# front.net
KiCad netlist of a schematic drawn in EAGLE
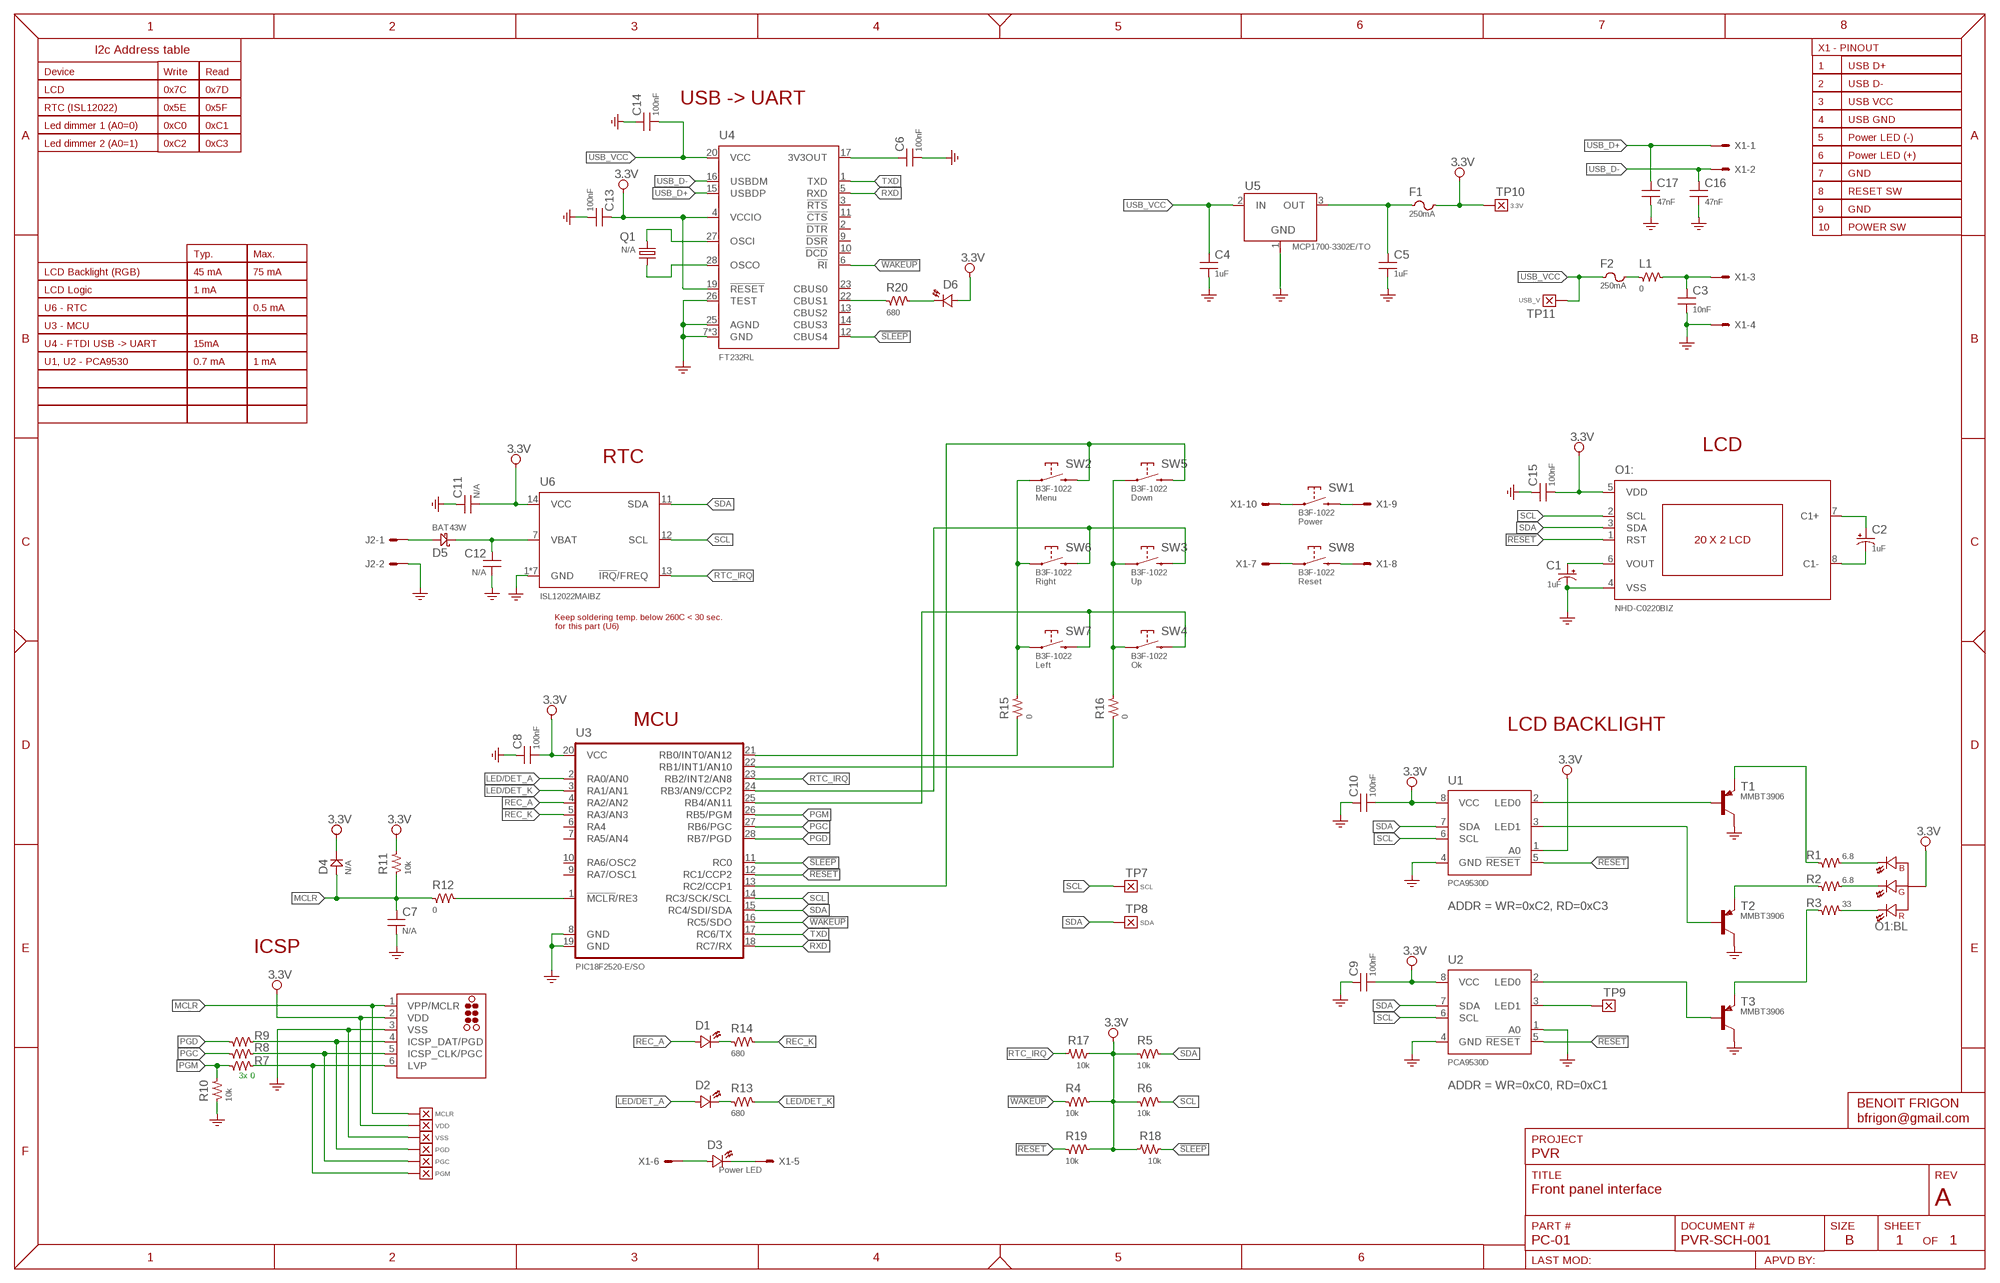
[diagram p0: schematic, sheet 1]

(export (version "E")
  (design (tool "Eeschema 10.0.6"))
  (components
    (comp (ref "C1")
      (value "1uF")
      (footprint "eagle-import:CAP_S0805")
      (libsource (lib "eagle-import") (part "CAP-E-S0805"))
    )
    (comp (ref "C2")
      (value "1uF")
      (footprint "eagle-import:CAP_S0805")
      (libsource (lib "eagle-import") (part "CAP-E-S0805"))
    )
    (comp (ref "C3")
      (value "10nF")
      (footprint "eagle-import:SMD_0805")
      (libsource (lib "eagle-import") (part "CAP-0805"))
    )
    (comp (ref "C4")
      (value "1uF")
      (footprint "eagle-import:SMD_0805")
      (libsource (lib "eagle-import") (part "CAP-0805"))
    )
    (comp (ref "C5")
      (value "1uF")
      (footprint "eagle-import:SMD_0805")
      (libsource (lib "eagle-import") (part "CAP-0805"))
    )
    (comp (ref "C6")
      (value "100nF")
      (footprint "eagle-import:SMD_0603")
      (libsource (lib "eagle-import") (part "CAP-0603"))
    )
    (comp (ref "C7")
      (value "N/A")
      (footprint "eagle-import:SMD_0603")
      (libsource (lib "eagle-import") (part "CAP-0603"))
    )
    (comp (ref "C8")
      (value "100nF")
      (footprint "eagle-import:SMD_0603")
      (libsource (lib "eagle-import") (part "CAP-0603"))
    )
    (comp (ref "C9")
      (value "100nF")
      (footprint "eagle-import:SMD_0603")
      (libsource (lib "eagle-import") (part "CAP-0603"))
    )
    (comp (ref "C10")
      (value "100nF")
      (footprint "eagle-import:SMD_0603")
      (libsource (lib "eagle-import") (part "CAP-0603"))
    )
    (comp (ref "C11")
      (value "N/A")
      (footprint "eagle-import:SMD_0603")
      (libsource (lib "eagle-import") (part "CAP-0603"))
    )
    (comp (ref "C12")
      (value "N/A")
      (footprint "eagle-import:SMD_0805")
      (libsource (lib "eagle-import") (part "CAP-0805"))
    )
    (comp (ref "C13")
      (value "100nF")
      (footprint "eagle-import:SMD_0603")
      (libsource (lib "eagle-import") (part "CAP-0603"))
    )
    (comp (ref "C14")
      (value "100nF")
      (footprint "eagle-import:SMD_0603")
      (description "{DESCRIPTION} - SMT 0603 - {value}")
      (fields (field (name "PACKAGE") "SMT 0603"))
      (libsource (lib "eagle-import") (part "CAP-0603"))
    )
    (comp (ref "C15")
      (value "100nF")
      (footprint "eagle-import:SMD_0603")
      (libsource (lib "eagle-import") (part "CAP-0603"))
    )
    (comp (ref "C16")
      (value "47nF")
      (footprint "eagle-import:SMD_0603")
      (libsource (lib "eagle-import") (part "CAP-0603"))
    )
    (comp (ref "C17")
      (value "47nF")
      (footprint "eagle-import:SMD_0603")
      (libsource (lib "eagle-import") (part "CAP-0603"))
    )
    (comp (ref "D1")
      (value "{ATTR:COLOR}")
      (footprint "eagle-import:LED_2X5")
      (fields (field (name "COLOR") "Red"))
      (libsource (lib "eagle-import") (part "LED-2X5"))
    )
    (comp (ref "D2")
      (value "{ATTR:COLOR}")
      (footprint "eagle-import:LED_2X5")
      (libsource (lib "eagle-import") (part "LED-2X5"))
    )
    (comp (ref "D3")
      (value "{ATTR:COLOR}")
      (footprint "eagle-import:LED_2X5")
      (fields (field (name "ID") "Power LED"))
      (libsource (lib "eagle-import") (part "LED-2X5"))
    )
    (comp (ref "D4")
      (value "N/A")
      (footprint "eagle-import:DIODE_0603")
      (libsource (lib "eagle-import") (part "DIODE-0603"))
    )
    (comp (ref "D5")
      (value "BAT43W")
      (footprint "eagle-import:SOD-323")
      (libsource (lib "eagle-import") (part "DIODE_SCHOTTKY-SOD323"))
    )
    (comp (ref "D6")
      (value "LED-0805")
      (footprint "eagle-import:CHIPLED_0805")
      (libsource (lib "eagle-import") (part "LED-0805"))
    )
    (comp (ref "F1")
      (value "250mA")
      (footprint "eagle-import:SMD_1206")
      (libsource (lib "eagle-import") (part "FUSE1206"))
    )
    (comp (ref "F2")
      (value "250mA")
      (footprint "eagle-import:SMD_1206")
      (libsource (lib "eagle-import") (part "FUSE1206"))
    )
    (comp (ref "J1")
      (value "TC2030-MCP")
      (footprint "eagle-import:TC2030-MCP")
      (fields (field (name "MFG") "Tag-Connect"))
      (libsource (lib "eagle-import") (part "TC2030-MCP"))
    )
    (comp (ref "J2")
      (value "SNG-2MM-HEADER-02-V")
      (footprint "eagle-import:DF3X-2P-2DSA")
      (fields (field (name "MFG") "Hirose Electronic") (field (name "NO_BOM") "1"))
      (libsource (lib "eagle-import") (part "SNG-2MM-HEADER-02-V"))
    )
    (comp (ref "L1")
      (value "0")
      (footprint "eagle-import:SMD_0805")
      (libsource (lib "eagle-import") (part "RES-0805"))
    )
    (comp (ref "O1")
      (value "NHD-C0220BIZ")
      (footprint "eagle-import:NHD-CO220BIZ")
      (fields (field (name "MFG") "Newheaven Display"))
      (libsource (lib "eagle-import") (part "NHD-C0220BIZ"))
    )
    (comp (ref "Q1")
      (value "N/A")
      (footprint "eagle-import:MM20SS")
      (libsource (lib "eagle-import") (part "XTALMM20SS"))
    )
    (comp (ref "R1")
      (value "6.8")
      (footprint "eagle-import:SMD_1206")
      (description "{DESCRIPTION} - SMT 1206 - {VALUE}")
      (fields (field (name "PACKAGE") "SMT 1206"))
      (libsource (lib "eagle-import") (part "RES-1206"))
    )
    (comp (ref "R2")
      (value "6.8")
      (footprint "eagle-import:SMD_1206")
      (description "{DESCRIPTION} - SMT 1206 - {VALUE}")
      (fields (field (name "PACKAGE") "SMT 1206"))
      (libsource (lib "eagle-import") (part "RES-1206"))
    )
    (comp (ref "R3")
      (value "33")
      (footprint "eagle-import:SMD_1206")
      (description "{DESCRIPTION} - SMT 1206 - {VALUE}")
      (fields (field (name "PACKAGE") "SMT 1206"))
      (libsource (lib "eagle-import") (part "RES-1206"))
    )
    (comp (ref "R4")
      (value "10k")
      (footprint "eagle-import:SMD_0805")
      (libsource (lib "eagle-import") (part "RES-0805"))
    )
    (comp (ref "R5")
      (value "10k")
      (footprint "eagle-import:SMD_0805")
      (libsource (lib "eagle-import") (part "RES-0805"))
    )
    (comp (ref "R6")
      (value "10k")
      (footprint "eagle-import:SMD_0805")
      (libsource (lib "eagle-import") (part "RES-0805"))
    )
    (comp (ref "R7")
      (value "0")
      (footprint "eagle-import:SMD_0603")
      (description "{DESCRIPTION} - SMT 0603 - {VALUE}")
      (fields (field (name "PACKAGE") "SMT 0603"))
      (libsource (lib "eagle-import") (part "RES-0603"))
    )
    (comp (ref "R8")
      (value "0")
      (footprint "eagle-import:SMD_0603")
      (description "{DESCRIPTION} - SMT 0603 - {VALUE}")
      (fields (field (name "PACKAGE") "SMT 0603"))
      (libsource (lib "eagle-import") (part "RES-0603"))
    )
    (comp (ref "R9")
      (value "0")
      (footprint "eagle-import:SMD_0603")
      (description "{DESCRIPTION} - SMT 0603 - {VALUE}")
      (fields (field (name "PACKAGE") "SMT 0603"))
      (libsource (lib "eagle-import") (part "RES-0603"))
    )
    (comp (ref "R10")
      (value "10k")
      (footprint "eagle-import:SMD_0603")
      (description "{DESCRIPTION} - SMT 0603 - {VALUE}")
      (fields (field (name "PACKAGE") "SMT 0603"))
      (libsource (lib "eagle-import") (part "RES-0603"))
    )
    (comp (ref "R11")
      (value "10k")
      (footprint "eagle-import:SMD_0603")
      (libsource (lib "eagle-import") (part "RES-0603"))
    )
    (comp (ref "R12")
      (value "0")
      (footprint "eagle-import:SMD_0603")
      (libsource (lib "eagle-import") (part "RES-0603"))
    )
    (comp (ref "R13")
      (value "680")
      (footprint "eagle-import:SMD_0805")
      (libsource (lib "eagle-import") (part "RES-0805"))
    )
    (comp (ref "R14")
      (value "680")
      (footprint "eagle-import:SMD_0805")
      (description "{DESCRIPTION} - SMT 0805 - {VALUE}")
      (fields (field (name "PACKAGE") "SMT 0805"))
      (libsource (lib "eagle-import") (part "RES-0805"))
    )
    (comp (ref "R15")
      (value "0")
      (footprint "eagle-import:SMD_0805")
      (libsource (lib "eagle-import") (part "RES-0805"))
    )
    (comp (ref "R16")
      (value "0")
      (footprint "eagle-import:SMD_0805")
      (libsource (lib "eagle-import") (part "RES-0805"))
    )
    (comp (ref "R17")
      (value "10k")
      (footprint "eagle-import:SMD_0603")
      (description "{DESCRIPTION} - SMT 0603 - {VALUE}")
      (fields (field (name "PACKAGE") "SMT 0603"))
      (libsource (lib "eagle-import") (part "RES-0603"))
    )
    (comp (ref "R18")
      (value "10k")
      (footprint "eagle-import:SMD_0805")
      (description "{DESCRIPTION} - SMT 0805 - {VALUE}")
      (fields (field (name "PACKAGE") "SMT 0805"))
      (libsource (lib "eagle-import") (part "RES-0805"))
    )
    (comp (ref "R19")
      (value "10k")
      (footprint "eagle-import:SMD_0805")
      (description "{DESCRIPTION} - SMT 0805 - {VALUE}")
      (fields (field (name "PACKAGE") "SMT 0805"))
      (libsource (lib "eagle-import") (part "RES-0805"))
    )
    (comp (ref "R20")
      (value "680")
      (footprint "eagle-import:SMD_0805")
      (libsource (lib "eagle-import") (part "RES-0805"))
    )
    (comp (ref "SW1")
      (value "B3F-1022")
      (footprint "eagle-import:B3F-10XX")
      (fields (field (name "MFG") "Omron Electronics") (field (name "KEY") "Power"))
      (libsource (lib "eagle-import") (part "B3F-?1022"))
    )
    (comp (ref "SW2")
      (value "B3F-1022")
      (footprint "eagle-import:B3F-10XX")
      (fields (field (name "MFG") "Omron Electronics") (field (name "KEY") "Menu"))
      (libsource (lib "eagle-import") (part "B3F-?1022"))
    )
    (comp (ref "SW3")
      (value "B3F-1022")
      (footprint "eagle-import:B3F-10XX")
      (fields (field (name "MFG") "Omron Electronics") (field (name "KEY") "Up"))
      (libsource (lib "eagle-import") (part "B3F-?1022"))
    )
    (comp (ref "SW4")
      (value "B3F-1022")
      (footprint "eagle-import:B3F-10XX")
      (fields (field (name "MFG") "Omron Electronics") (field (name "KEY") "Ok"))
      (libsource (lib "eagle-import") (part "B3F-?1022"))
    )
    (comp (ref "SW5")
      (value "B3F-1022")
      (footprint "eagle-import:B3F-10XX")
      (fields (field (name "MFG") "Omron Electronics") (field (name "KEY") "Down"))
      (libsource (lib "eagle-import") (part "B3F-?1022"))
    )
    (comp (ref "SW6")
      (value "B3F-1022")
      (footprint "eagle-import:B3F-10XX")
      (fields (field (name "MFG") "Omron Electronics") (field (name "KEY") "Right"))
      (libsource (lib "eagle-import") (part "B3F-?1022"))
    )
    (comp (ref "SW7")
      (value "B3F-1022")
      (footprint "eagle-import:B3F-10XX")
      (fields (field (name "MFG") "Omron Electronics") (field (name "KEY") "Left"))
      (libsource (lib "eagle-import") (part "B3F-?1022"))
    )
    (comp (ref "SW8")
      (value "B3F-1022")
      (footprint "eagle-import:B3F-10XX")
      (fields (field (name "MFG") "Omron Electronics") (field (name "KEY") "Reset"))
      (libsource (lib "eagle-import") (part "B3F-?1022"))
    )
    (comp (ref "T1")
      (value "MMBT3906")
      (footprint "eagle-import:SOT23-BEC")
      (libsource (lib "eagle-import") (part "-PNP-SOT23-BEC"))
    )
    (comp (ref "T2")
      (value "MMBT3906")
      (footprint "eagle-import:SOT23-BEC")
      (fields (field (name "SKU") "{VALUE}"))
      (libsource (lib "eagle-import") (part "-PNP-SOT23-BEC"))
    )
    (comp (ref "T3")
      (value "MMBT3906")
      (footprint "eagle-import:SOT23-BEC")
      (fields (field (name "SKU") "{VALUE}"))
      (libsource (lib "eagle-import") (part "-PNP-SOT23-BEC"))
    )
    (comp (ref "TP1")
      (value "MCLR")
      (footprint "eagle-import:TP_050")
      (libsource (lib "eagle-import") (part "TEST_POINT-050"))
    )
    (comp (ref "TP2")
      (value "VDD")
      (footprint "eagle-import:TP_050")
      (libsource (lib "eagle-import") (part "TEST_POINT-050"))
    )
    (comp (ref "TP3")
      (value "VSS")
      (footprint "eagle-import:TP_050")
      (libsource (lib "eagle-import") (part "TEST_POINT-050"))
    )
    (comp (ref "TP4")
      (value "PGD")
      (footprint "eagle-import:TP_050")
      (libsource (lib "eagle-import") (part "TEST_POINT-050"))
    )
    (comp (ref "TP5")
      (value "PGC")
      (footprint "eagle-import:TP_050")
      (libsource (lib "eagle-import") (part "TEST_POINT-050"))
    )
    (comp (ref "TP6")
      (value "PGM")
      (footprint "eagle-import:TP_050")
      (libsource (lib "eagle-import") (part "TEST_POINT-050"))
    )
    (comp (ref "TP7")
      (value "SCL")
      (footprint "eagle-import:TP_050")
      (libsource (lib "eagle-import") (part "TEST_POINT-050"))
    )
    (comp (ref "TP8")
      (value "SDA")
      (footprint "eagle-import:TP_050")
      (libsource (lib "eagle-import") (part "TEST_POINT-050"))
    )
    (comp (ref "TP9")
      (value "TEST_POINT-050")
      (footprint "eagle-import:TP_050")
      (libsource (lib "eagle-import") (part "TEST_POINT-050"))
    )
    (comp (ref "TP10")
      (value "3.3V")
      (footprint "eagle-import:TP_050")
      (libsource (lib "eagle-import") (part "TEST_POINT-050"))
    )
    (comp (ref "TP11")
      (value "USB_V")
      (footprint "eagle-import:TP_050")
      (libsource (lib "eagle-import") (part "TEST_POINT-050"))
    )
    (comp (ref "U1")
      (value "PCA9530D")
      (footprint "eagle-import:SOIC8")
      (fields (field (name "MFG") "NXP Semiconductors") (field (name "ADDR") "WR=0xC2, RD=0xC3"))
      (libsource (lib "eagle-import") (part "PCA9530D"))
    )
    (comp (ref "U2")
      (value "PCA9530D")
      (footprint "eagle-import:SOIC8")
      (fields (field (name "MFG") "NXP Semiconductors") (field (name "ADDR") "WR=0xC0, RD=0xC1"))
      (libsource (lib "eagle-import") (part "PCA9530D"))
    )
    (comp (ref "U3")
      (value "PIC18F2520-E/SO")
      (footprint "eagle-import:SOIC28")
      (libsource (lib "eagle-import") (part "PIC18F520-?E/SO2"))
    )
    (comp (ref "U4")
      (value "FT232RL")
      (footprint "eagle-import:SSOP28")
      (libsource (lib "eagle-import") (part "FT232RL"))
    )
    (comp (ref "U5")
      (value "MCP1700-3302E/TO")
      (footprint "eagle-import:TO92")
      (fields (field (name "MFG") "Microchip"))
      (libsource (lib "eagle-import") (part "MCP1700-?TO3302E/"))
    )
    (comp (ref "U6")
      (value "ISL12022MAIBZ")
      (footprint "eagle-import:SOIC20W")
      (libsource (lib "eagle-import") (part "ISL12022MAIBZ"))
    )
    (comp (ref "X1")
      (value "DL-100-HEADER-10-V")
      (footprint "eagle-import:534206-5")
      (fields
        (field (name "MFG") "Tyco Electronics")
        (field (name "MFG_1") "Sullins Connector Solutions")
        (field (name "SKU") "SIP110-PPPC-D05-ST-BK")
      )
      (libsource (lib "eagle-import") (part "DL-100-HEADER-10-V"))
    )
  )
  (nets
    (net (code "1") (name "/~{RESET}") (class "Default")
      (node (ref "O1") (pin "1") (pinfunction "RST_1") (pintype "bidirectional"))
      (node (ref "R19") (pin "1") (pinfunction "1_1") (pintype "passive"))
      (node (ref "U1") (pin "5") (pinfunction "~{RESET}_5") (pintype "input"))
      (node (ref "U2") (pin "5") (pinfunction "~{RESET}_5") (pintype "input"))
      (node (ref "U3") (pin "12") (pinfunction "RC1/CCP2_12") (pintype "bidirectional"))
    )
    (net (code "2") (name "/~{SLEEP}") (class "Default")
      (node (ref "R18") (pin "1") (pinfunction "1_1") (pintype "passive"))
      (node (ref "U3") (pin "11") (pinfunction "RC0_11") (pintype "bidirectional"))
      (node (ref "U4") (pin "12") (pinfunction "CBUS4_12") (pintype "bidirectional"))
    )
    (net (code "3") (name "/~{WAKEUP}") (class "Default")
      (node (ref "R4") (pin "1") (pinfunction "1_1") (pintype "passive"))
      (node (ref "U3") (pin "16") (pinfunction "RC5/SDO_16") (pintype "bidirectional"))
      (node (ref "U4") (pin "6") (pinfunction "~{RI}_6") (pintype "bidirectional"))
    )
    (net (code "4") (name "3.3V") (class "Default")
      (node (ref "C10") (pin "2") (pinfunction "2_2") (pintype "passive"))
      (node (ref "C11") (pin "2") (pinfunction "2_2") (pintype "passive"))
      (node (ref "C13") (pin "1") (pinfunction "1_1") (pintype "passive"))
      (node (ref "C15") (pin "2") (pinfunction "2_2") (pintype "passive"))
      (node (ref "C8") (pin "2") (pinfunction "2_2") (pintype "passive"))
      (node (ref "C9") (pin "2") (pinfunction "2_2") (pintype "passive"))
      (node (ref "D4") (pin "K") (pinfunction "K_K") (pintype "passive"))
      (node (ref "D6") (pin "A") (pinfunction "A_A") (pintype "passive"))
      (node (ref "F1") (pin "2") (pinfunction "2_2") (pintype "passive"))
      (node (ref "J1") (pin "2") (pinfunction "VDD_2") (pintype "power_in"))
      (node (ref "O1") (pin "5") (pinfunction "VDD_5") (pintype "bidirectional"))
      (node (ref "O1") (pin "A") (pinfunction "A_A") (pintype "passive"))
      (node (ref "R11") (pin "2") (pinfunction "2_2") (pintype "passive"))
      (node (ref "R17") (pin "1") (pinfunction "1_1") (pintype "passive"))
      (node (ref "R18") (pin "2") (pinfunction "2_2") (pintype "passive"))
      (node (ref "R19") (pin "2") (pinfunction "2_2") (pintype "passive"))
      (node (ref "R4") (pin "2") (pinfunction "2_2") (pintype "passive"))
      (node (ref "R5") (pin "1") (pinfunction "1_1") (pintype "passive"))
      (node (ref "R6") (pin "1") (pinfunction "1_1") (pintype "passive"))
      (node (ref "TP10") (pin "1") (pinfunction "P$1_1") (pintype "bidirectional"))
      (node (ref "TP2") (pin "1") (pinfunction "P$1_1") (pintype "bidirectional"))
      (node (ref "U1") (pin "1") (pinfunction "A0_1") (pintype "bidirectional"))
      (node (ref "U1") (pin "8") (pinfunction "VCC_8") (pintype "power_in"))
      (node (ref "U2") (pin "8") (pinfunction "VCC_8") (pintype "power_in"))
      (node (ref "U3") (pin "20") (pinfunction "VCC_20") (pintype "power_in"))
      (node (ref "U4") (pin "19") (pinfunction "~{RESET}_19") (pintype "bidirectional"))
      (node (ref "U4") (pin "4") (pinfunction "VCCIO_4") (pintype "bidirectional"))
      (node (ref "U6") (pin "14") (pinfunction "VCC_14") (pintype "bidirectional"))
    )
    (net (code "5") (name "GND") (class "Default")
      (node (ref "C1") (pin "-") (pinfunction "-_-") (pintype "passive"))
      (node (ref "C10") (pin "1") (pinfunction "1_1") (pintype "passive"))
      (node (ref "C11") (pin "1") (pinfunction "1_1") (pintype "passive"))
      (node (ref "C12") (pin "2") (pinfunction "2_2") (pintype "passive"))
      (node (ref "C13") (pin "2") (pinfunction "2_2") (pintype "passive"))
      (node (ref "C14") (pin "1") (pinfunction "1_1") (pintype "passive"))
      (node (ref "C15") (pin "1") (pinfunction "1_1") (pintype "passive"))
      (node (ref "C16") (pin "2") (pinfunction "2_2") (pintype "passive"))
      (node (ref "C17") (pin "2") (pinfunction "2_2") (pintype "passive"))
      (node (ref "C3") (pin "2") (pinfunction "2_2") (pintype "passive"))
      (node (ref "C4") (pin "2") (pinfunction "2_2") (pintype "passive"))
      (node (ref "C5") (pin "2") (pinfunction "2_2") (pintype "passive"))
      (node (ref "C6") (pin "2") (pinfunction "2_2") (pintype "passive"))
      (node (ref "C7") (pin "2") (pinfunction "2_2") (pintype "passive"))
      (node (ref "C8") (pin "1") (pinfunction "1_1") (pintype "passive"))
      (node (ref "C9") (pin "1") (pinfunction "1_1") (pintype "passive"))
      (node (ref "J1") (pin "3") (pinfunction "VSS_3") (pintype "power_in"))
      (node (ref "J2") (pin "2") (pinfunction "S_2") (pintype "bidirectional"))
      (node (ref "O1") (pin "4") (pinfunction "VSS_4") (pintype "bidirectional"))
      (node (ref "R10") (pin "1") (pinfunction "1_1") (pintype "passive"))
      (node (ref "T1") (pin "C") (pinfunction "C_C") (pintype "passive"))
      (node (ref "T2") (pin "C") (pinfunction "C_C") (pintype "passive"))
      (node (ref "T3") (pin "C") (pinfunction "C_C") (pintype "passive"))
      (node (ref "TP3") (pin "1") (pinfunction "P$1_1") (pintype "bidirectional"))
      (node (ref "U1") (pin "4") (pinfunction "GND_4") (pintype "power_in"))
      (node (ref "U2") (pin "1") (pinfunction "A0_1") (pintype "bidirectional"))
      (node (ref "U2") (pin "4") (pinfunction "GND_4") (pintype "power_in"))
      (node (ref "U3") (pin "19") (pinfunction "GND_19") (pintype "power_in"))
      (node (ref "U3") (pin "8") (pinfunction "GND_8") (pintype "power_in"))
      (node (ref "U4") (pin "18") (pinfunction "GND_18") (pintype "bidirectional"))
      (node (ref "U4") (pin "21") (pinfunction "GND_21") (pintype "bidirectional"))
      (node (ref "U4") (pin "25") (pinfunction "AGND_25") (pintype "bidirectional"))
      (node (ref "U4") (pin "26") (pinfunction "TEST_26") (pintype "bidirectional"))
      (node (ref "U4") (pin "7") (pinfunction "GND_7") (pintype "bidirectional"))
      (node (ref "U5") (pin "1") (pinfunction "GND_1") (pintype "power_in"))
      (node (ref "U6") (pin "1") (pinfunction "GND_1") (pintype "bidirectional"))
      (node (ref "U6") (pin "18") (pinfunction "GND_18") (pintype "bidirectional"))
      (node (ref "U6") (pin "19") (pinfunction "GND_19") (pintype "bidirectional"))
      (node (ref "U6") (pin "2") (pinfunction "GND_2") (pintype "bidirectional"))
      (node (ref "U6") (pin "20") (pinfunction "GND_20") (pintype "bidirectional"))
      (node (ref "U6") (pin "3") (pinfunction "GND_3") (pintype "bidirectional"))
      (node (ref "U6") (pin "8") (pinfunction "GND_8") (pintype "bidirectional"))
      (node (ref "X1") (pin "4") (pinfunction "S_4") (pintype "bidirectional"))
    )
    (net (code "6") (name "LED{slash}DET_A") (class "Default")
      (node (ref "D2") (pin "A") (pinfunction "A_A") (pintype "passive"))
      (node (ref "U3") (pin "2") (pinfunction "RA0/AN0_2") (pintype "bidirectional"))
    )
    (net (code "7") (name "LED{slash}DET_K") (class "Default")
      (node (ref "R13") (pin "2") (pinfunction "2_2") (pintype "passive"))
      (node (ref "U3") (pin "3") (pinfunction "RA1/AN1_3") (pintype "bidirectional"))
    )
    (net (code "8") (name "MCLR") (class "Default")
      (node (ref "C7") (pin "1") (pinfunction "1_1") (pintype "passive"))
      (node (ref "D4") (pin "A") (pinfunction "A_A") (pintype "passive"))
      (node (ref "J1") (pin "1") (pinfunction "VPP/MCLR_1") (pintype "passive"))
      (node (ref "R11") (pin "1") (pinfunction "1_1") (pintype "passive"))
      (node (ref "R12") (pin "1") (pinfunction "1_1") (pintype "passive"))
      (node (ref "TP1") (pin "1") (pinfunction "P$1_1") (pintype "bidirectional"))
    )
    (net (code "9") (name "Net-(D1-PadK)") (class "Default")
      (node (ref "D1") (pin "K") (pinfunction "K_K") (pintype "passive"))
      (node (ref "R14") (pin "1") (pinfunction "1_1") (pintype "passive"))
    )
    (net (code "10") (name "Net-(D2-PadK)") (class "Default")
      (node (ref "D2") (pin "K") (pinfunction "K_K") (pintype "passive"))
      (node (ref "R13") (pin "1") (pinfunction "1_1") (pintype "passive"))
    )
    (net (code "11") (name "Net-(D6-PadK)") (class "Default")
      (node (ref "D6") (pin "K") (pinfunction "K_K") (pintype "passive"))
      (node (ref "R20") (pin "2") (pinfunction "2_2") (pintype "passive"))
    )
    (net (code "12") (name "Net-(F2-Pad2)") (class "Default")
      (node (ref "F2") (pin "2") (pinfunction "2_2") (pintype "passive"))
      (node (ref "L1") (pin "1") (pinfunction "1_1") (pintype "passive"))
    )
    (net (code "13") (name "Net-(J1-ICSP_CLK{slash}PGC)") (class "Default")
      (node (ref "J1") (pin "5") (pinfunction "ICSP_CLK/PGC_5") (pintype "output"))
      (node (ref "R8") (pin "2") (pinfunction "2_2") (pintype "passive"))
      (node (ref "TP5") (pin "1") (pinfunction "P$1_1") (pintype "bidirectional"))
    )
    (net (code "14") (name "Net-(J1-ICSP_DAT{slash}PGD)") (class "Default")
      (node (ref "J1") (pin "4") (pinfunction "ICSP_DAT/PGD_4") (pintype "bidirectional"))
      (node (ref "R9") (pin "2") (pinfunction "2_2") (pintype "passive"))
      (node (ref "TP4") (pin "1") (pinfunction "P$1_1") (pintype "bidirectional"))
    )
    (net (code "15") (name "Net-(J1-LVP)") (class "Default")
      (node (ref "J1") (pin "6") (pinfunction "LVP_6") (pintype "bidirectional"))
      (node (ref "R7") (pin "2") (pinfunction "2_2") (pintype "passive"))
      (node (ref "TP6") (pin "1") (pinfunction "P$1_1") (pintype "bidirectional"))
    )
    (net (code "16") (name "Net-(J2A-S)") (class "Default")
      (node (ref "D5") (pin "A") (pinfunction "A_A") (pintype "passive"))
      (node (ref "J2") (pin "1") (pinfunction "S_1") (pintype "bidirectional"))
    )
    (net (code "17") (name "Net-(O1-PadBK)") (class "Default")
      (node (ref "O1") (pin "BK") (pinfunction "BK_BK") (pintype "passive"))
      (node (ref "R1") (pin "2") (pinfunction "2_2") (pintype "passive"))
    )
    (net (code "18") (name "Net-(O1-PadGK)") (class "Default")
      (node (ref "O1") (pin "GK") (pinfunction "GK_GK") (pintype "passive"))
      (node (ref "R2") (pin "2") (pinfunction "2_2") (pintype "passive"))
    )
    (net (code "19") (name "Net-(O1-PadRK)") (class "Default")
      (node (ref "O1") (pin "RK") (pinfunction "RK_RK") (pintype "passive"))
      (node (ref "R3") (pin "2") (pinfunction "2_2") (pintype "passive"))
    )
    (net (code "20") (name "Net-(O1A-C1+)") (class "Default")
      (node (ref "C2") (pin "+") (pinfunction "+_+") (pintype "passive"))
      (node (ref "O1") (pin "7") (pinfunction "C1+_7") (pintype "bidirectional"))
    )
    (net (code "21") (name "Net-(O1A-C1-)") (class "Default")
      (node (ref "C2") (pin "-") (pinfunction "-_-") (pintype "passive"))
      (node (ref "O1") (pin "8") (pinfunction "C1-_8") (pintype "bidirectional"))
    )
    (net (code "22") (name "Net-(O1A-VOUT)") (class "Default")
      (node (ref "C1") (pin "+") (pinfunction "+_+") (pintype "passive"))
      (node (ref "O1") (pin "6") (pinfunction "VOUT_6") (pintype "bidirectional"))
    )
    (net (code "23") (name "Net-(Q1-2)") (class "Default")
      (node (ref "Q1") (pin "4") (pinfunction "2_4") (pintype "passive"))
      (node (ref "U4") (pin "28") (pinfunction "OSCO_28") (pintype "bidirectional"))
    )
    (net (code "24") (name "Net-(R1-Pad1)") (class "Default")
      (node (ref "R1") (pin "1") (pinfunction "1_1") (pintype "passive"))
      (node (ref "T1") (pin "E") (pinfunction "E_E") (pintype "passive"))
    )
    (net (code "25") (name "Net-(R2-Pad1)") (class "Default")
      (node (ref "R2") (pin "1") (pinfunction "1_1") (pintype "passive"))
      (node (ref "T2") (pin "E") (pinfunction "E_E") (pintype "passive"))
    )
    (net (code "26") (name "Net-(R3-Pad1)") (class "Default")
      (node (ref "R3") (pin "1") (pinfunction "1_1") (pintype "passive"))
      (node (ref "T3") (pin "E") (pinfunction "E_E") (pintype "passive"))
    )
    (net (code "27") (name "Net-(R15-Pad2)") (class "Default")
      (node (ref "R15") (pin "2") (pinfunction "2_2") (pintype "passive"))
      (node (ref "SW2") (pin "3") (pinfunction "1_3") (pintype "passive"))
      (node (ref "SW2") (pin "4") (pinfunction "1_4") (pintype "passive"))
      (node (ref "SW6") (pin "3") (pinfunction "1_3") (pintype "passive"))
      (node (ref "SW6") (pin "4") (pinfunction "1_4") (pintype "passive"))
      (node (ref "SW7") (pin "3") (pinfunction "1_3") (pintype "passive"))
      (node (ref "SW7") (pin "4") (pinfunction "1_4") (pintype "passive"))
    )
    (net (code "28") (name "Net-(R16-Pad2)") (class "Default")
      (node (ref "R16") (pin "2") (pinfunction "2_2") (pintype "passive"))
      (node (ref "SW3") (pin "3") (pinfunction "1_3") (pintype "passive"))
      (node (ref "SW3") (pin "4") (pinfunction "1_4") (pintype "passive"))
      (node (ref "SW4") (pin "3") (pinfunction "1_3") (pintype "passive"))
      (node (ref "SW4") (pin "4") (pinfunction "1_4") (pintype "passive"))
      (node (ref "SW5") (pin "3") (pinfunction "1_3") (pintype "passive"))
      (node (ref "SW5") (pin "4") (pinfunction "1_4") (pintype "passive"))
    )
    (net (code "29") (name "Net-(TP9-P$1)") (class "Default")
      (node (ref "TP9") (pin "1") (pinfunction "P$1_1") (pintype "bidirectional"))
      (node (ref "U2") (pin "3") (pinfunction "LED1_3") (pintype "output"))
    )
    (net (code "30") (name "Net-(U1-LED0)") (class "Default")
      (node (ref "T1") (pin "B") (pinfunction "B_B") (pintype "passive"))
      (node (ref "U1") (pin "2") (pinfunction "LED0_2") (pintype "output"))
    )
    (net (code "31") (name "Net-(U1-LED1)") (class "Default")
      (node (ref "T2") (pin "B") (pinfunction "B_B") (pintype "passive"))
      (node (ref "U1") (pin "3") (pinfunction "LED1_3") (pintype "output"))
    )
    (net (code "32") (name "Net-(U2-LED0)") (class "Default")
      (node (ref "T3") (pin "B") (pinfunction "B_B") (pintype "passive"))
      (node (ref "U2") (pin "2") (pinfunction "LED0_2") (pintype "output"))
    )
    (net (code "33") (name "Net-(U3-RB0{slash}INT0{slash}AN12)") (class "Default")
      (node (ref "R15") (pin "1") (pinfunction "1_1") (pintype "passive"))
      (node (ref "U3") (pin "21") (pinfunction "RB0/INT0/AN12_21") (pintype "bidirectional"))
    )
    (net (code "34") (name "Net-(U3-RB1{slash}INT1{slash}AN10)") (class "Default")
      (node (ref "R16") (pin "1") (pinfunction "1_1") (pintype "passive"))
      (node (ref "U3") (pin "22") (pinfunction "RB1/INT1/AN10_22") (pintype "bidirectional"))
    )
    (net (code "35") (name "Net-(U3-RB3{slash}AN9{slash}CCP2)") (class "Default")
      (node (ref "SW3") (pin "1") (pinfunction "2_1") (pintype "passive"))
      (node (ref "SW3") (pin "2") (pinfunction "2_2") (pintype "passive"))
      (node (ref "SW6") (pin "1") (pinfunction "2_1") (pintype "passive"))
      (node (ref "SW6") (pin "2") (pinfunction "2_2") (pintype "passive"))
      (node (ref "U3") (pin "24") (pinfunction "RB3/AN9/CCP2_24") (pintype "bidirectional"))
    )
    (net (code "36") (name "Net-(U3-RB4{slash}AN11)") (class "Default")
      (node (ref "SW4") (pin "1") (pinfunction "2_1") (pintype "passive"))
      (node (ref "SW4") (pin "2") (pinfunction "2_2") (pintype "passive"))
      (node (ref "SW7") (pin "1") (pinfunction "2_1") (pintype "passive"))
      (node (ref "SW7") (pin "2") (pinfunction "2_2") (pintype "passive"))
      (node (ref "U3") (pin "25") (pinfunction "RB4/AN11_25") (pintype "bidirectional"))
    )
    (net (code "37") (name "Net-(U3-RC2{slash}CCP1)") (class "Default")
      (node (ref "SW2") (pin "1") (pinfunction "2_1") (pintype "passive"))
      (node (ref "SW2") (pin "2") (pinfunction "2_2") (pintype "passive"))
      (node (ref "SW5") (pin "1") (pinfunction "2_1") (pintype "passive"))
      (node (ref "SW5") (pin "2") (pinfunction "2_2") (pintype "passive"))
      (node (ref "U3") (pin "13") (pinfunction "RC2/CCP1_13") (pintype "bidirectional"))
    )
    (net (code "38") (name "Net-(U3-~{MCLR}{slash}RE3)") (class "Default")
      (node (ref "R12") (pin "2") (pinfunction "2_2") (pintype "passive"))
      (node (ref "U3") (pin "1") (pinfunction "~{MCLR}/RE3_1") (pintype "bidirectional"))
    )
    (net (code "39") (name "Net-(U4-3V3OUT)") (class "Default")
      (node (ref "C6") (pin "1") (pinfunction "1_1") (pintype "passive"))
      (node (ref "U4") (pin "17") (pinfunction "3V3OUT_17") (pintype "bidirectional"))
    )
    (net (code "40") (name "Net-(U4-CBUS1)") (class "Default")
      (node (ref "R20") (pin "1") (pinfunction "1_1") (pintype "passive"))
      (node (ref "U4") (pin "22") (pinfunction "CBUS1_22") (pintype "bidirectional"))
    )
    (net (code "41") (name "Net-(U4-OSCI)") (class "Default")
      (node (ref "Q1") (pin "1") (pinfunction "1_1") (pintype "passive"))
      (node (ref "U4") (pin "27") (pinfunction "OSCI_27") (pintype "bidirectional"))
    )
    (net (code "42") (name "Net-(U5-OUT)") (class "Default")
      (node (ref "C5") (pin "1") (pinfunction "1_1") (pintype "passive"))
      (node (ref "F1") (pin "1") (pinfunction "1_1") (pintype "passive"))
      (node (ref "U5") (pin "3") (pinfunction "OUT_3") (pintype "power_in"))
    )
    (net (code "43") (name "Net-(U6-VBAT)") (class "Default")
      (node (ref "C12") (pin "1") (pinfunction "1_1") (pintype "passive"))
      (node (ref "D5") (pin "K") (pinfunction "K_K") (pintype "passive"))
      (node (ref "U6") (pin "7") (pinfunction "VBAT_7") (pintype "bidirectional"))
    )
    (net (code "44") (name "Net-(X1B-S)") (class "Default")
      (node (ref "SW1") (pin "3") (pinfunction "1_3") (pintype "passive"))
      (node (ref "SW1") (pin "4") (pinfunction "1_4") (pintype "passive"))
      (node (ref "X1") (pin "10") (pinfunction "S_10") (pintype "bidirectional"))
    )
    (net (code "45") (name "Net-(X1D-S)") (class "Default")
      (node (ref "C3") (pin "1") (pinfunction "1_1") (pintype "passive"))
      (node (ref "L1") (pin "2") (pinfunction "2_2") (pintype "passive"))
      (node (ref "X1") (pin "3") (pinfunction "S_3") (pintype "bidirectional"))
    )
    (net (code "46") (name "Net-(X1F-S)") (class "Default")
      (node (ref "D3") (pin "K") (pinfunction "K_K") (pintype "passive"))
      (node (ref "X1") (pin "5") (pinfunction "S_5") (pintype "bidirectional"))
    )
    (net (code "47") (name "Net-(X1G-S)") (class "Default")
      (node (ref "D3") (pin "A") (pinfunction "A_A") (pintype "passive"))
      (node (ref "X1") (pin "6") (pinfunction "S_6") (pintype "bidirectional"))
    )
    (net (code "48") (name "Net-(X1H-S)") (class "Default")
      (node (ref "SW8") (pin "3") (pinfunction "1_3") (pintype "passive"))
      (node (ref "SW8") (pin "4") (pinfunction "1_4") (pintype "passive"))
      (node (ref "X1") (pin "7") (pinfunction "S_7") (pintype "bidirectional"))
    )
    (net (code "49") (name "Net-(X1I-S)") (class "Default")
      (node (ref "SW8") (pin "1") (pinfunction "2_1") (pintype "passive"))
      (node (ref "SW8") (pin "2") (pinfunction "2_2") (pintype "passive"))
      (node (ref "X1") (pin "8") (pinfunction "S_8") (pintype "bidirectional"))
    )
    (net (code "50") (name "Net-(X1J-S)") (class "Default")
      (node (ref "SW1") (pin "1") (pinfunction "2_1") (pintype "passive"))
      (node (ref "SW1") (pin "2") (pinfunction "2_2") (pintype "passive"))
      (node (ref "X1") (pin "9") (pinfunction "S_9") (pintype "bidirectional"))
    )
    (net (code "51") (name "PGC") (class "Default")
      (node (ref "R8") (pin "1") (pinfunction "1_1") (pintype "passive"))
      (node (ref "U3") (pin "27") (pinfunction "RB6/PGC_27") (pintype "bidirectional"))
    )
    (net (code "52") (name "PGD") (class "Default")
      (node (ref "R9") (pin "1") (pinfunction "1_1") (pintype "passive"))
      (node (ref "U3") (pin "28") (pinfunction "RB7/PGD_28") (pintype "bidirectional"))
    )
    (net (code "53") (name "PGM") (class "Default")
      (node (ref "R10") (pin "2") (pinfunction "2_2") (pintype "passive"))
      (node (ref "R7") (pin "1") (pinfunction "1_1") (pintype "passive"))
      (node (ref "U3") (pin "26") (pinfunction "RB5/PGM_26") (pintype "bidirectional"))
    )
    (net (code "54") (name "REC_A") (class "Default")
      (node (ref "D1") (pin "A") (pinfunction "A_A") (pintype "passive"))
      (node (ref "U3") (pin "4") (pinfunction "RA2/AN2_4") (pintype "bidirectional"))
    )
    (net (code "55") (name "REC_K") (class "Default")
      (node (ref "R14") (pin "2") (pinfunction "2_2") (pintype "passive"))
      (node (ref "U3") (pin "5") (pinfunction "RA3/AN3_5") (pintype "bidirectional"))
    )
    (net (code "56") (name "RTC_IRQ") (class "Default")
      (node (ref "R17") (pin "2") (pinfunction "2_2") (pintype "passive"))
      (node (ref "U3") (pin "23") (pinfunction "RB2/INT2/AN8_23") (pintype "bidirectional"))
      (node (ref "U6") (pin "13") (pinfunction "~{IRQ}/FREQ_13") (pintype "bidirectional"))
    )
    (net (code "57") (name "RXD") (class "Default")
      (node (ref "U3") (pin "18") (pinfunction "RC7/RX_18") (pintype "bidirectional"))
      (node (ref "U4") (pin "5") (pinfunction "RXD_5") (pintype "bidirectional"))
    )
    (net (code "58") (name "SCL") (class "Default")
      (node (ref "O1") (pin "2") (pinfunction "SCL_2") (pintype "bidirectional"))
      (node (ref "R6") (pin "2") (pinfunction "2_2") (pintype "passive"))
      (node (ref "TP7") (pin "1") (pinfunction "P$1_1") (pintype "bidirectional"))
      (node (ref "U1") (pin "6") (pinfunction "SCL_6") (pintype "input"))
      (node (ref "U2") (pin "6") (pinfunction "SCL_6") (pintype "input"))
      (node (ref "U3") (pin "14") (pinfunction "RC3/SCK/SCL_14") (pintype "bidirectional"))
      (node (ref "U6") (pin "12") (pinfunction "SCL_12") (pintype "bidirectional"))
    )
    (net (code "59") (name "SDA") (class "Default")
      (node (ref "O1") (pin "3") (pinfunction "SDA_3") (pintype "bidirectional"))
      (node (ref "R5") (pin "2") (pinfunction "2_2") (pintype "passive"))
      (node (ref "TP8") (pin "1") (pinfunction "P$1_1") (pintype "bidirectional"))
      (node (ref "U1") (pin "7") (pinfunction "SDA_7") (pintype "bidirectional"))
      (node (ref "U2") (pin "7") (pinfunction "SDA_7") (pintype "bidirectional"))
      (node (ref "U3") (pin "15") (pinfunction "RC4/SDI/SDA_15") (pintype "bidirectional"))
      (node (ref "U6") (pin "11") (pinfunction "SDA_11") (pintype "bidirectional"))
    )
    (net (code "60") (name "TXD") (class "Default")
      (node (ref "U3") (pin "17") (pinfunction "RC6/TX_17") (pintype "bidirectional"))
      (node (ref "U4") (pin "1") (pinfunction "TXD_1") (pintype "bidirectional"))
    )
    (net (code "61") (name "USB_D+") (class "Default")
      (node (ref "C17") (pin "1") (pinfunction "1_1") (pintype "passive"))
      (node (ref "U4") (pin "15") (pinfunction "USBDP_15") (pintype "bidirectional"))
      (node (ref "X1") (pin "1") (pinfunction "S_1") (pintype "bidirectional"))
    )
    (net (code "62") (name "USB_D-") (class "Default")
      (node (ref "C16") (pin "1") (pinfunction "1_1") (pintype "passive"))
      (node (ref "U4") (pin "16") (pinfunction "USBDM_16") (pintype "bidirectional"))
      (node (ref "X1") (pin "2") (pinfunction "S_2") (pintype "bidirectional"))
    )
    (net (code "63") (name "USB_VCC") (class "Default")
      (node (ref "C14") (pin "2") (pinfunction "2_2") (pintype "passive"))
      (node (ref "C4") (pin "1") (pinfunction "1_1") (pintype "passive"))
      (node (ref "F2") (pin "1") (pinfunction "1_1") (pintype "passive"))
      (node (ref "TP11") (pin "1") (pinfunction "P$1_1") (pintype "bidirectional"))
      (node (ref "U4") (pin "20") (pinfunction "VCC_20") (pintype "bidirectional"))
      (node (ref "U5") (pin "2") (pinfunction "IN_2") (pintype "power_in"))
    )
    (net (code "64") (name "unconnected-(U3-RA4-Pad6)") (class "Default")
      (node (ref "U3") (pin "6") (pinfunction "RA4_6") (pintype "bidirectional"))
    )
    (net (code "65") (name "unconnected-(U3-RA5{slash}AN4-Pad7)") (class "Default")
      (node (ref "U3") (pin "7") (pinfunction "RA5/AN4_7") (pintype "bidirectional"))
    )
    (net (code "66") (name "unconnected-(U3-RA6{slash}OSC2-Pad10)") (class "Default")
      (node (ref "U3") (pin "10") (pinfunction "RA6/OSC2_10") (pintype "bidirectional"))
    )
    (net (code "67") (name "unconnected-(U3-RA7{slash}OSC1-Pad9)") (class "Default")
      (node (ref "U3") (pin "9") (pinfunction "RA7/OSC1_9") (pintype "bidirectional"))
    )
    (net (code "68") (name "unconnected-(U4-CBUS0-Pad23)") (class "Default")
      (node (ref "U4") (pin "23") (pinfunction "CBUS0_23") (pintype "bidirectional"))
    )
    (net (code "69") (name "unconnected-(U4-CBUS2-Pad13)") (class "Default")
      (node (ref "U4") (pin "13") (pinfunction "CBUS2_13") (pintype "bidirectional"))
    )
    (net (code "70") (name "unconnected-(U4-CBUS3-Pad14)") (class "Default")
      (node (ref "U4") (pin "14") (pinfunction "CBUS3_14") (pintype "bidirectional"))
    )
    (net (code "71") (name "unconnected-(U4-~{CTS}-Pad11)") (class "Default")
      (node (ref "U4") (pin "11") (pinfunction "~{CTS}_11") (pintype "bidirectional"))
    )
    (net (code "72") (name "unconnected-(U4-~{DCD}-Pad10)") (class "Default")
      (node (ref "U4") (pin "10") (pinfunction "~{DCD}_10") (pintype "bidirectional"))
    )
    (net (code "73") (name "unconnected-(U4-~{DSR}-Pad9)") (class "Default")
      (node (ref "U4") (pin "9") (pinfunction "~{DSR}_9") (pintype "bidirectional"))
    )
    (net (code "74") (name "unconnected-(U4-~{DTR}-Pad2)") (class "Default")
      (node (ref "U4") (pin "2") (pinfunction "~{DTR}_2") (pintype "bidirectional"))
    )
    (net (code "75") (name "unconnected-(U4-~{RTS}-Pad3)") (class "Default")
      (node (ref "U4") (pin "3") (pinfunction "~{RTS}_3") (pintype "bidirectional"))
    )
  )
)
